# sidi-base.net
KiCad netlist of a schematic drawn in EAGLE
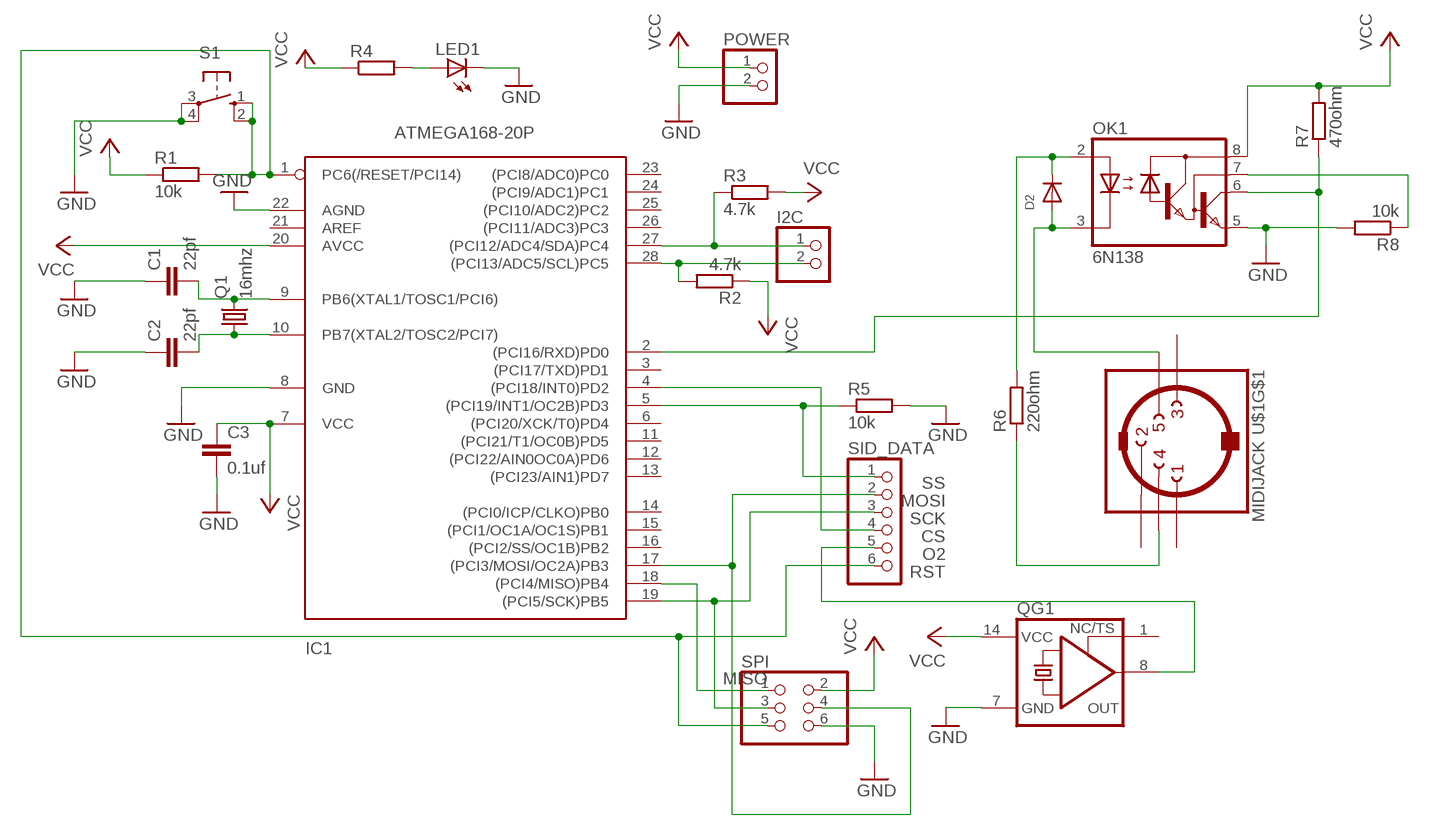
[diagram p0: schematic, sheet 1]

(export (version "E")
  (design (tool "Eeschema 10.0.6"))
  (components
    (comp (ref "C1")
      (value "22pf")
      (footprint "eagle-import:C050-050X075")
      (libsource (lib "eagle-import") (part "C-EU050-050X075"))
    )
    (comp (ref "C2")
      (value "22pf")
      (footprint "eagle-import:C050-050X075")
      (libsource (lib "eagle-import") (part "C-EU050-050X075"))
    )
    (comp (ref "C3")
      (value "0.1uf")
      (footprint "eagle-import:C050-050X075")
      (libsource (lib "eagle-import") (part "C-EU050-050X075"))
    )
    (comp (ref "D2")
      (value "DIODEDO-1N4148")
      (footprint "eagle-import:DO-1N4148")
      (libsource (lib "eagle-import") (part "DIODEDO-1N4148"))
    )
    (comp (ref "I2C")
      (value "PINHD-1X2")
      (footprint "eagle-import:1X02")
      (libsource (lib "eagle-import") (part "PINHD-1X2"))
    )
    (comp (ref "IC1")
      (value "ATMEGA168-20P")
      (footprint "eagle-import:DIL28-3")
      (libsource (lib "eagle-import") (part "ATMEGA168P-20"))
    )
    (comp (ref "LED1")
      (value "LED3MM")
      (footprint "eagle-import:LED3MM")
      (libsource (lib "eagle-import") (part "LED3MM"))
    )
    (comp (ref "OK1")
      (value "6N138")
      (footprint "eagle-import:DIL08")
      (fields (field (name "MF") "VISHAY/TELEFUNKEN"))
      (libsource (lib "eagle-import") (part "6N138"))
    )
    (comp (ref "POWER")
      (value "PINHD-1X2")
      (footprint "eagle-import:1X02")
      (libsource (lib "eagle-import") (part "PINHD-1X2"))
    )
    (comp (ref "Q1")
      (value "16mhz")
      (footprint "eagle-import:HC49_S")
      (libsource (lib "eagle-import") (part "CRYSTALHC49S"))
    )
    (comp (ref "QG1")
      (value "XO-14")
      (footprint "eagle-import:DIL14S")
      (libsource (lib "eagle-import") (part "XO-14"))
    )
    (comp (ref "R1")
      (value "10k")
      (footprint "eagle-import:0207_7")
      (libsource (lib "eagle-import") (part "R-EU_0207/7"))
    )
    (comp (ref "R2")
      (value "4.7k")
      (footprint "eagle-import:0207_7")
      (libsource (lib "eagle-import") (part "R-EU_0207/7"))
    )
    (comp (ref "R3")
      (value "4.7k")
      (footprint "eagle-import:0207_7")
      (libsource (lib "eagle-import") (part "R-EU_0207/7"))
    )
    (comp (ref "R4")
      (value "R-EU_0207/7")
      (footprint "eagle-import:0207_7")
      (libsource (lib "eagle-import") (part "R-EU_0207/7"))
    )
    (comp (ref "R5")
      (value "10k")
      (footprint "eagle-import:0207_7")
      (libsource (lib "eagle-import") (part "R-EU_0207/7"))
    )
    (comp (ref "R6")
      (value "220ohm")
      (footprint "eagle-import:0207_7")
      (libsource (lib "eagle-import") (part "R-EU_0207/7"))
    )
    (comp (ref "R7")
      (value "470ohm")
      (footprint "eagle-import:0207_7")
      (libsource (lib "eagle-import") (part "R-EU_0207/7"))
    )
    (comp (ref "R8")
      (value "10k")
      (footprint "eagle-import:0207_7")
      (libsource (lib "eagle-import") (part "R-EU_0207/7"))
    )
    (comp (ref "S1")
      (value "10-XX")
      (footprint "eagle-import:B3F-10XX")
      (fields (field (name "MPN") "B3F-1000"))
      (libsource (lib "eagle-import") (part "10-XX"))
    )
    (comp (ref "SID_DATA")
      (value "PINHD-1X6")
      (footprint "eagle-import:1X06")
      (libsource (lib "eagle-import") (part "PINHD-1X6"))
    )
    (comp (ref "SPI")
      (value "PINHD-2X3")
      (footprint "eagle-import:2X03")
      (libsource (lib "eagle-import") (part "PINHD-2X3"))
    )
    (comp (ref "U$1")
      (value "MIDIJACK")
      (footprint "eagle-import:CP-2350")
      (libsource (lib "eagle-import") (part "MIDIJACK"))
    )
  )
  (nets
    (net (code "1") (name "/CS") (class "Default")
      (node (ref "IC1") (pin "4") (pinfunction "(PCI18/INT0)PD2_4") (pintype "bidirectional"))
      (node (ref "SID_DATA") (pin "4") (pinfunction "4_4") (pintype "passive"))
    )
    (net (code "2") (name "/MISO") (class "Default")
      (node (ref "IC1") (pin "18") (pinfunction "(PCI4/MISO)PB4_18") (pintype "bidirectional"))
      (node (ref "SPI") (pin "1") (pinfunction "1_1") (pintype "passive"))
    )
    (net (code "3") (name "/MOSI") (class "Default")
      (node (ref "IC1") (pin "17") (pinfunction "(PCI3/MOSI/OC2A)PB3_17") (pintype "bidirectional"))
      (node (ref "SID_DATA") (pin "2") (pinfunction "2_2") (pintype "passive"))
      (node (ref "SPI") (pin "4") (pinfunction "4_4") (pintype "passive"))
    )
    (net (code "4") (name "/O2") (class "Default")
      (node (ref "QG1") (pin "8") (pinfunction "OUT_8") (pintype "output"))
      (node (ref "SID_DATA") (pin "5") (pinfunction "5_5") (pintype "passive"))
    )
    (net (code "5") (name "/RST") (class "Default")
      (node (ref "IC1") (pin "1") (pinfunction "PC6(/RESET/PCI14)_1") (pintype "bidirectional"))
      (node (ref "R1") (pin "2") (pinfunction "2_2") (pintype "passive"))
      (node (ref "S1") (pin "1") (pinfunction "S_1") (pintype "passive"))
      (node (ref "S1") (pin "2") (pinfunction "S1_2") (pintype "passive"))
      (node (ref "SID_DATA") (pin "6") (pinfunction "6_6") (pintype "passive"))
      (node (ref "SPI") (pin "5") (pinfunction "5_5") (pintype "passive"))
    )
    (net (code "6") (name "/SCK") (class "Default")
      (node (ref "IC1") (pin "19") (pinfunction "(PCI5/SCK)PB5_19") (pintype "bidirectional"))
      (node (ref "SID_DATA") (pin "3") (pinfunction "3_3") (pintype "passive"))
      (node (ref "SPI") (pin "3") (pinfunction "3_3") (pintype "passive"))
    )
    (net (code "7") (name "/SS") (class "Default")
      (node (ref "IC1") (pin "5") (pinfunction "(PCI19/INT1/OC2B)PD3_5") (pintype "bidirectional"))
      (node (ref "R5") (pin "1") (pinfunction "1_1") (pintype "passive"))
      (node (ref "SID_DATA") (pin "1") (pinfunction "1_1") (pintype "passive"))
    )
    (net (code "8") (name "GND") (class "Default")
      (node (ref "C1") (pin "1") (pinfunction "1_1") (pintype "passive"))
      (node (ref "C2") (pin "1") (pinfunction "1_1") (pintype "passive"))
      (node (ref "C3") (pin "2") (pinfunction "2_2") (pintype "passive"))
      (node (ref "IC1") (pin "22") (pinfunction "AGND_22") (pintype "bidirectional"))
      (node (ref "IC1") (pin "8") (pinfunction "GND_8") (pintype "bidirectional"))
      (node (ref "LED1") (pin "K") (pinfunction "C_K") (pintype "passive"))
      (node (ref "OK1") (pin "5") (pinfunction "GND_5") (pintype "passive"))
      (node (ref "POWER") (pin "2") (pinfunction "2_2") (pintype "passive"))
      (node (ref "QG1") (pin "7") (pinfunction "GND_7") (pintype "power_in"))
      (node (ref "R5") (pin "2") (pinfunction "2_2") (pintype "passive"))
      (node (ref "R8") (pin "2") (pinfunction "2_2") (pintype "passive"))
      (node (ref "S1") (pin "3") (pinfunction "P_3") (pintype "passive"))
      (node (ref "S1") (pin "4") (pinfunction "P1_4") (pintype "passive"))
      (node (ref "SPI") (pin "6") (pinfunction "6_6") (pintype "passive"))
    )
    (net (code "9") (name "Net-(IC1-(PCI12{slash}ADC4{slash}SDA)PC4)") (class "Default")
      (node (ref "I2C") (pin "1") (pinfunction "1_1") (pintype "passive"))
      (node (ref "IC1") (pin "27") (pinfunction "(PCI12/ADC4/SDA)PC4_27") (pintype "bidirectional"))
      (node (ref "R3") (pin "1") (pinfunction "1_1") (pintype "passive"))
    )
    (net (code "10") (name "Net-(IC1-(PCI13{slash}ADC5{slash}SCL)PC5)") (class "Default")
      (node (ref "I2C") (pin "2") (pinfunction "2_2") (pintype "passive"))
      (node (ref "IC1") (pin "28") (pinfunction "(PCI13/ADC5/SCL)PC5_28") (pintype "bidirectional"))
      (node (ref "R2") (pin "2") (pinfunction "2_2") (pintype "passive"))
    )
    (net (code "11") (name "Net-(IC1-(PCI16{slash}RXD)PD0)") (class "Default")
      (node (ref "IC1") (pin "2") (pinfunction "(PCI16/RXD)PD0_2") (pintype "bidirectional"))
      (node (ref "OK1") (pin "6") (pinfunction "VO_6") (pintype "passive"))
      (node (ref "R7") (pin "1") (pinfunction "1_1") (pintype "passive"))
    )
    (net (code "12") (name "Net-(IC1-PB6(XTAL1{slash}TOSC1{slash}PCI6))") (class "Default")
      (node (ref "C1") (pin "2") (pinfunction "2_2") (pintype "passive"))
      (node (ref "IC1") (pin "9") (pinfunction "PB6(XTAL1/TOSC1/PCI6)_9") (pintype "bidirectional"))
      (node (ref "Q1") (pin "2") (pinfunction "2_2") (pintype "passive"))
    )
    (net (code "13") (name "Net-(IC1-PB7(XTAL2{slash}TOSC2{slash}PCI7))") (class "Default")
      (node (ref "C2") (pin "2") (pinfunction "2_2") (pintype "passive"))
      (node (ref "IC1") (pin "10") (pinfunction "PB7(XTAL2/TOSC2/PCI7)_10") (pintype "bidirectional"))
      (node (ref "Q1") (pin "1") (pinfunction "1_1") (pintype "passive"))
    )
    (net (code "14") (name "Net-(LED1-PadA)") (class "Default")
      (node (ref "LED1") (pin "A") (pinfunction "A_A") (pintype "passive"))
      (node (ref "R4") (pin "2") (pinfunction "2_2") (pintype "passive"))
    )
    (net (code "15") (name "Net-(OK1-A)") (class "Default")
      (node (ref "D2") (pin "C") (pinfunction "C_C") (pintype "passive"))
      (node (ref "OK1") (pin "2") (pinfunction "A_2") (pintype "passive"))
      (node (ref "R6") (pin "2") (pinfunction "2_2") (pintype "passive"))
    )
    (net (code "16") (name "Net-(OK1-C)") (class "Default")
      (node (ref "D2") (pin "A") (pinfunction "A_A") (pintype "passive"))
      (node (ref "OK1") (pin "3") (pinfunction "C_3") (pintype "passive"))
      (node (ref "U$1") (pin "5") (pinfunction "5_5") (pintype "passive"))
    )
    (net (code "17") (name "Net-(OK1-VB)") (class "Default")
      (node (ref "OK1") (pin "7") (pinfunction "VB_7") (pintype "passive"))
      (node (ref "R8") (pin "1") (pinfunction "1_1") (pintype "passive"))
    )
    (net (code "18") (name "Net-(R6-Pad1)") (class "Default")
      (node (ref "R6") (pin "1") (pinfunction "1_1") (pintype "passive"))
      (node (ref "U$1") (pin "4") (pinfunction "4_4") (pintype "passive"))
    )
    (net (code "19") (name "VCC") (class "Default")
      (node (ref "C3") (pin "1") (pinfunction "1_1") (pintype "passive"))
      (node (ref "IC1") (pin "20") (pinfunction "AVCC_20") (pintype "bidirectional"))
      (node (ref "IC1") (pin "7") (pinfunction "VCC_7") (pintype "bidirectional"))
      (node (ref "OK1") (pin "8") (pinfunction "VCC_8") (pintype "passive"))
      (node (ref "POWER") (pin "1") (pinfunction "1_1") (pintype "passive"))
      (node (ref "QG1") (pin "14") (pinfunction "VCC_14") (pintype "power_in"))
      (node (ref "R1") (pin "1") (pinfunction "1_1") (pintype "passive"))
      (node (ref "R2") (pin "1") (pinfunction "1_1") (pintype "passive"))
      (node (ref "R3") (pin "2") (pinfunction "2_2") (pintype "passive"))
      (node (ref "R4") (pin "1") (pinfunction "1_1") (pintype "passive"))
      (node (ref "R7") (pin "2") (pinfunction "2_2") (pintype "passive"))
      (node (ref "SPI") (pin "2") (pinfunction "2_2") (pintype "passive"))
    )
    (net (code "20") (name "unconnected-(IC1-(PCI0{slash}ICP{slash}CLKO)PB0-Pad14)") (class "Default")
      (node (ref "IC1") (pin "14") (pinfunction "(PCI0/ICP/CLKO)PB0_14") (pintype "bidirectional"))
    )
    (net (code "21") (name "unconnected-(IC1-(PCI1{slash}OC1A{slash}OC1S)PB1-Pad15)") (class "Default")
      (node (ref "IC1") (pin "15") (pinfunction "(PCI1/OC1A/OC1S)PB1_15") (pintype "bidirectional"))
    )
    (net (code "22") (name "unconnected-(IC1-(PCI2{slash}SS{slash}OC1B)PB2-Pad16)") (class "Default")
      (node (ref "IC1") (pin "16") (pinfunction "(PCI2/SS/OC1B)PB2_16") (pintype "bidirectional"))
    )
    (net (code "23") (name "unconnected-(IC1-(PCI8{slash}ADC0)PC0-Pad23)") (class "Default")
      (node (ref "IC1") (pin "23") (pinfunction "(PCI8/ADC0)PC0_23") (pintype "bidirectional"))
    )
    (net (code "24") (name "unconnected-(IC1-(PCI9{slash}ADC1)PC1-Pad24)") (class "Default")
      (node (ref "IC1") (pin "24") (pinfunction "(PCI9/ADC1)PC1_24") (pintype "bidirectional"))
    )
    (net (code "25") (name "unconnected-(IC1-(PCI10{slash}ADC2)PC2-Pad25)") (class "Default")
      (node (ref "IC1") (pin "25") (pinfunction "(PCI10/ADC2)PC2_25") (pintype "bidirectional"))
    )
    (net (code "26") (name "unconnected-(IC1-(PCI11{slash}ADC3)PC3-Pad26)") (class "Default")
      (node (ref "IC1") (pin "26") (pinfunction "(PCI11/ADC3)PC3_26") (pintype "bidirectional"))
    )
    (net (code "27") (name "unconnected-(IC1-(PCI17{slash}TXD)PD1-Pad3)") (class "Default")
      (node (ref "IC1") (pin "3") (pinfunction "(PCI17/TXD)PD1_3") (pintype "bidirectional"))
    )
    (net (code "28") (name "unconnected-(IC1-(PCI20{slash}XCK{slash}T0)PD4-Pad6)") (class "Default")
      (node (ref "IC1") (pin "6") (pinfunction "(PCI20/XCK/T0)PD4_6") (pintype "bidirectional"))
    )
    (net (code "29") (name "unconnected-(IC1-(PCI21{slash}T1{slash}OC0B)PD5-Pad11)") (class "Default")
      (node (ref "IC1") (pin "11") (pinfunction "(PCI21/T1/OC0B)PD5_11") (pintype "bidirectional"))
    )
    (net (code "30") (name "unconnected-(IC1-(PCI22{slash}AIN0OC0A)PD6-Pad12)") (class "Default")
      (node (ref "IC1") (pin "12") (pinfunction "(PCI22/AIN0OC0A)PD6_12") (pintype "bidirectional"))
    )
    (net (code "31") (name "unconnected-(IC1-(PCI23{slash}AIN1)PD7-Pad13)") (class "Default")
      (node (ref "IC1") (pin "13") (pinfunction "(PCI23/AIN1)PD7_13") (pintype "bidirectional"))
    )
    (net (code "32") (name "unconnected-(IC1-AREF-Pad21)") (class "Default")
      (node (ref "IC1") (pin "21") (pinfunction "AREF_21") (pintype "bidirectional"))
    )
    (net (code "33") (name "unconnected-(QG1-TS-Pad1)") (class "Default")
      (node (ref "QG1") (pin "1") (pinfunction "TS_1") (pintype "passive"))
    )
    (net (code "34") (name "unconnected-(U$1-Pad1)") (class "Default")
      (node (ref "U$1") (pin "1") (pinfunction "1_1") (pintype "passive"))
    )
    (net (code "35") (name "unconnected-(U$1-Pad2)") (class "Default")
      (node (ref "U$1") (pin "2") (pinfunction "2_2") (pintype "passive"))
    )
    (net (code "36") (name "unconnected-(U$1-Pad3)") (class "Default")
      (node (ref "U$1") (pin "3") (pinfunction "3_3") (pintype "passive"))
    )
  )
)
